# 7c_-_FET_Controls.net
KiCad netlist of a schematic drawn in Altium Designer
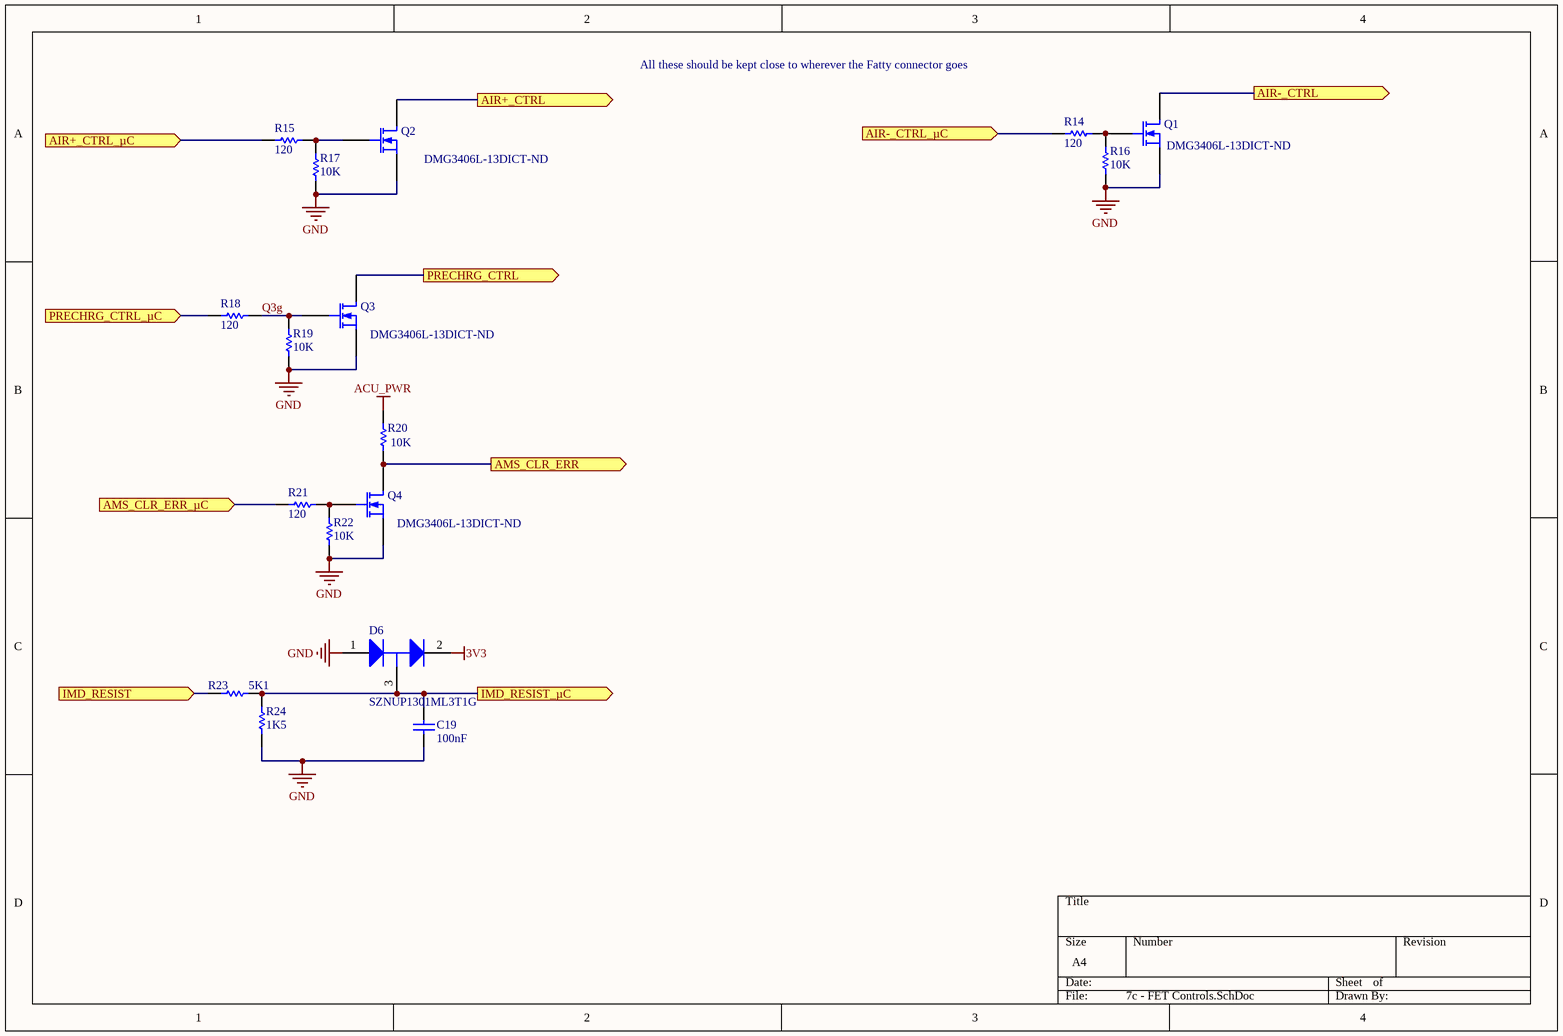
[diagram p0: 7c - FET Controls.SchDoc]

(export (version "E")
  (design (tool "Eeschema 10.0.6"))
  (components
    (comp (ref "C19")
      (value "100nF")
      (footprint "1608[0603]")
      (description "Capacitor")
      (fields (field (name "Comment") "Cap") (field (name "PUBLISHER") "Altium Limited"))
      (libsource (lib "Miscellaneous Devices") (part "Cap"))
    )
    (comp (ref "D6")
      (value "SZNUP1301ML3T1G")
      (footprint "ONSC-SOT-23-3-318-08_V")
      (fields (field (name "MANUFACTURER") "On Semiconductor"))
      (libsource (lib "Altium Content Vault") (part "ONSC-NUP1301-SOT-23-3-318-08"))
    )
    (comp (ref "Q1")
      (value "~")
      (footprint "SOT-23_N")
      (description "N-Channel MOSFET")
      (fields
        (field (name "MANUFACTURER") "Infineon Technologies")
        (field (name "MANUFACTURER PART NUMBER") "IPD075N03L G")
        (field (name "SUPPLIER PART NUMBER 1") "DMG3406L-13DICT-ND")
        (field (name "PUBLISHER") "Altium Limited")
      )
      (libsource (lib "Miscellaneous Devices") (part "MOSFET-N"))
    )
    (comp (ref "Q2")
      (value "~")
      (footprint "SOT-23_N")
      (description "N-Channel MOSFET")
      (fields
        (field (name "MANUFACTURER") "Infineon Technologies")
        (field (name "MANUFACTURER PART NUMBER") "IPD075N03L G")
        (field (name "SUPPLIER PART NUMBER 1") "DMG3406L-13DICT-ND")
        (field (name "PUBLISHER") "Altium Limited")
      )
      (libsource (lib "Miscellaneous Devices") (part "MOSFET-N"))
    )
    (comp (ref "Q3")
      (value "~")
      (footprint "SOT-23_N")
      (description "N-Channel MOSFET")
      (fields
        (field (name "MANUFACTURER") "Infineon Technologies")
        (field (name "MANUFACTURER PART NUMBER") "IPD075N03L G")
        (field (name "SUPPLIER PART NUMBER 1") "DMG3406L-13DICT-ND")
        (field (name "PUBLISHER") "Altium Limited")
      )
      (libsource (lib "Miscellaneous Devices") (part "MOSFET-N"))
    )
    (comp (ref "Q4")
      (value "~")
      (footprint "SOT-23_N")
      (description "N-Channel MOSFET")
      (fields
        (field (name "MANUFACTURER") "Infineon Technologies")
        (field (name "MANUFACTURER PART NUMBER") "IPD075N03L G")
        (field (name "SUPPLIER PART NUMBER 1") "DMG3406L-13DICT-ND")
        (field (name "PUBLISHER") "Altium Limited")
      )
      (libsource (lib "Miscellaneous Devices") (part "MOSFET-N"))
    )
    (comp (ref "R14")
      (value "120")
      (footprint "1608[0603]")
      (description "Resistor")
      (fields (field (name "PUBLISHER") "Altium Limited"))
      (libsource (lib "Miscellaneous Devices") (part "Res1"))
    )
    (comp (ref "R15")
      (value "120")
      (footprint "1608[0603]")
      (description "Resistor")
      (fields (field (name "PUBLISHER") "Altium Limited"))
      (libsource (lib "Miscellaneous Devices") (part "Res1"))
    )
    (comp (ref "R16")
      (value "10K")
      (footprint "1608[0603]")
      (description "Resistor")
      (fields (field (name "PUBLISHER") "Altium Limited"))
      (libsource (lib "Miscellaneous Devices") (part "Res1"))
    )
    (comp (ref "R17")
      (value "10K")
      (footprint "1608[0603]")
      (description "Resistor")
      (fields (field (name "PUBLISHER") "Altium Limited"))
      (libsource (lib "Miscellaneous Devices") (part "Res1"))
    )
    (comp (ref "R18")
      (value "120")
      (footprint "1608[0603]")
      (description "Resistor")
      (fields (field (name "PUBLISHER") "Altium Limited"))
      (libsource (lib "Miscellaneous Devices") (part "Res1"))
    )
    (comp (ref "R19")
      (value "10K")
      (footprint "1608[0603]")
      (description "Resistor")
      (fields (field (name "PUBLISHER") "Altium Limited"))
      (libsource (lib "Miscellaneous Devices") (part "Res1"))
    )
    (comp (ref "R20")
      (value "10K")
      (footprint "1608[0603]")
      (description "Resistor")
      (fields (field (name "PUBLISHER") "Altium Limited"))
      (libsource (lib "Miscellaneous Devices") (part "Res1"))
    )
    (comp (ref "R21")
      (value "120")
      (footprint "1608[0603]")
      (description "Resistor")
      (fields (field (name "PUBLISHER") "Altium Limited"))
      (libsource (lib "Miscellaneous Devices") (part "Res1"))
    )
    (comp (ref "R22")
      (value "10K")
      (footprint "1608[0603]")
      (description "Resistor")
      (fields (field (name "PUBLISHER") "Altium Limited"))
      (libsource (lib "Miscellaneous Devices") (part "Res1"))
    )
    (comp (ref "R23")
      (value "5K1")
      (footprint "1608[0603]")
      (description "Resistor")
      (fields (field (name "Comment") "Res1") (field (name "PUBLISHER") "Altium Limited"))
      (libsource (lib "Miscellaneous Devices") (part "Res1"))
    )
    (comp (ref "R24")
      (value "1K5")
      (footprint "1608[0603]")
      (description "Resistor")
      (fields (field (name "Comment") "Res1") (field (name "PUBLISHER") "Altium Limited"))
      (libsource (lib "Miscellaneous Devices") (part "Res1"))
    )
  )
  (nets
    (net (code "1") (name "/AIR+_CTRL") (class "Default")
      (node (ref "Q2") (pin "3") (pinfunction "D_3") (pintype "passive"))
    )
    (net (code "2") (name "/AIR+_CTRL_µC") (class "Default")
      (node (ref "R15") (pin "1") (pinfunction "1_1") (pintype "passive"))
    )
    (net (code "3") (name "/AIR-_CTRL") (class "Default")
      (node (ref "Q1") (pin "3") (pinfunction "D_3") (pintype "passive"))
    )
    (net (code "4") (name "/AIR-_CTRL_µC") (class "Default")
      (node (ref "R14") (pin "1") (pinfunction "1_1") (pintype "passive"))
    )
    (net (code "5") (name "/AMS_CLR_ERR") (class "Default")
      (node (ref "Q4") (pin "3") (pinfunction "D_3") (pintype "passive"))
      (node (ref "R20") (pin "1") (pinfunction "1_1") (pintype "passive"))
    )
    (net (code "6") (name "/AMS_CLR_ERR_µC") (class "Default")
      (node (ref "R21") (pin "1") (pinfunction "1_1") (pintype "passive"))
    )
    (net (code "7") (name "/IMD_RESIST") (class "Default")
      (node (ref "R23") (pin "1") (pinfunction "1_1") (pintype "passive"))
    )
    (net (code "8") (name "/IMD_RESIST_µC") (class "Default")
      (node (ref "C19") (pin "2") (pinfunction "2_2") (pintype "passive"))
      (node (ref "D6") (pin "3") (pinfunction "K/A_3") (pintype "passive"))
      (node (ref "R23") (pin "2") (pinfunction "2_2") (pintype "passive"))
      (node (ref "R24") (pin "2") (pinfunction "2_2") (pintype "passive"))
    )
    (net (code "9") (name "/PRECHRG_CTRL") (class "Default")
      (node (ref "Q3") (pin "3") (pinfunction "D_3") (pintype "passive"))
    )
    (net (code "10") (name "/PRECHRG_CTRL_µC") (class "Default")
      (node (ref "R18") (pin "1") (pinfunction "1_1") (pintype "passive"))
    )
    (net (code "11") (name "/Q3g") (class "Default")
      (node (ref "Q3") (pin "1") (pinfunction "G_1") (pintype "passive"))
      (node (ref "R18") (pin "2") (pinfunction "2_2") (pintype "passive"))
      (node (ref "R19") (pin "2") (pinfunction "2_2") (pintype "passive"))
    )
    (net (code "12") (name "3V3") (class "Default")
      (node (ref "D6") (pin "2") (pinfunction "K_2") (pintype "passive"))
    )
    (net (code "13") (name "ACU_PWR") (class "Default")
      (node (ref "R20") (pin "2") (pinfunction "2_2") (pintype "passive"))
    )
    (net (code "14") (name "GND") (class "Default")
      (node (ref "C19") (pin "1") (pinfunction "1_1") (pintype "passive"))
      (node (ref "D6") (pin "1") (pinfunction "A_1") (pintype "passive"))
      (node (ref "Q1") (pin "2") (pinfunction "S_2") (pintype "passive"))
      (node (ref "Q2") (pin "2") (pinfunction "S_2") (pintype "passive"))
      (node (ref "Q3") (pin "2") (pinfunction "S_2") (pintype "passive"))
      (node (ref "Q4") (pin "2") (pinfunction "S_2") (pintype "passive"))
      (node (ref "R16") (pin "1") (pinfunction "1_1") (pintype "passive"))
      (node (ref "R17") (pin "1") (pinfunction "1_1") (pintype "passive"))
      (node (ref "R19") (pin "1") (pinfunction "1_1") (pintype "passive"))
      (node (ref "R22") (pin "1") (pinfunction "1_1") (pintype "passive"))
      (node (ref "R24") (pin "1") (pinfunction "1_1") (pintype "passive"))
    )
    (net (code "15") (name "Net-(Q1-G)") (class "Default")
      (node (ref "Q1") (pin "1") (pinfunction "G_1") (pintype "passive"))
      (node (ref "R14") (pin "2") (pinfunction "2_2") (pintype "passive"))
      (node (ref "R16") (pin "2") (pinfunction "2_2") (pintype "passive"))
    )
    (net (code "16") (name "Net-(Q2-G)") (class "Default")
      (node (ref "Q2") (pin "1") (pinfunction "G_1") (pintype "passive"))
      (node (ref "R15") (pin "2") (pinfunction "2_2") (pintype "passive"))
      (node (ref "R17") (pin "2") (pinfunction "2_2") (pintype "passive"))
    )
    (net (code "17") (name "Net-(Q4-G)") (class "Default")
      (node (ref "Q4") (pin "1") (pinfunction "G_1") (pintype "passive"))
      (node (ref "R21") (pin "2") (pinfunction "2_2") (pintype "passive"))
      (node (ref "R22") (pin "2") (pinfunction "2_2") (pintype "passive"))
    )
  )
)
